# Montecarlo.net
KiCad netlist of a schematic drawn in Altium Designer
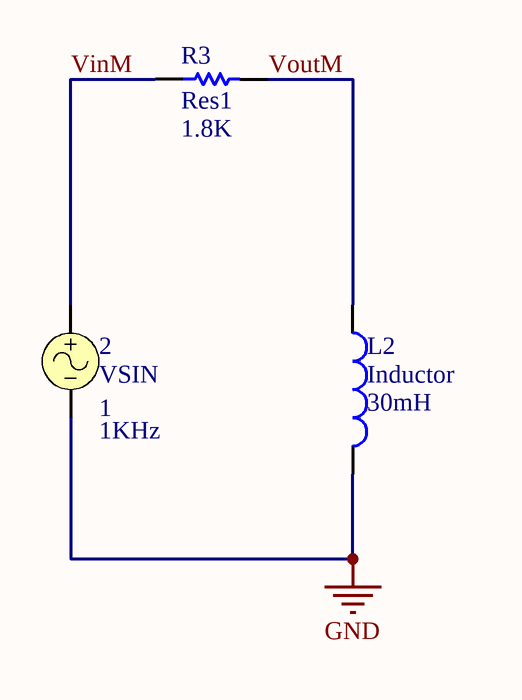
[diagram p0: Montecarlo.SchDoc]

(export (version "E")
  (design (tool "Eeschema 10.0.6"))
  (components
    (comp (ref "2")
      (value "VSIN")
      (description "Sinusoidal Voltage Source")
      (fields
        (field (name "AMPLITUDE") "1")
        (field (name "FREQUENCY") "1KHz")
        (field (name "PUBLISHER") "Altium Limited")
      )
      (libsource (lib "Simulation Sources") (part "VSIN"))
    )
    (comp (ref "L2")
      (value "Inductor")
      (footprint "0402-A")
      (fields (field (name "ALTIUM_VALUE") "30mH") (field (name "PUBLISHER") "Altium Limited"))
      (libsource (lib "Miscellaneous Devices") (part "Inductor"))
    )
    (comp (ref "R3")
      (value "Res1")
      (footprint "AXIAL-0.3")
      (description "Resistor")
      (fields (field (name "ALTIUM_VALUE") "1.8K") (field (name "PUBLISHER") "Altium Limited"))
      (libsource (lib "Miscellaneous Devices") (part "Res1"))
    )
  )
  (nets
    (net (code "1") (name "/VinM") (class "Default")
      (node (ref "2") (pin "1") (pinfunction "1_1") (pintype "passive"))
      (node (ref "R3") (pin "1") (pinfunction "1_1") (pintype "passive"))
    )
    (net (code "2") (name "/VoutM") (class "Default")
      (node (ref "L2") (pin "1") (pinfunction "1_1") (pintype "passive"))
      (node (ref "R3") (pin "2") (pinfunction "2_2") (pintype "passive"))
    )
    (net (code "3") (name "GND") (class "Default")
      (node (ref "2") (pin "2") (pinfunction "2_2") (pintype "passive"))
      (node (ref "L2") (pin "2") (pinfunction "2_2") (pintype "passive"))
    )
  )
)
